# Blinky_board.net
KiCad netlist of a schematic drawn in EAGLE
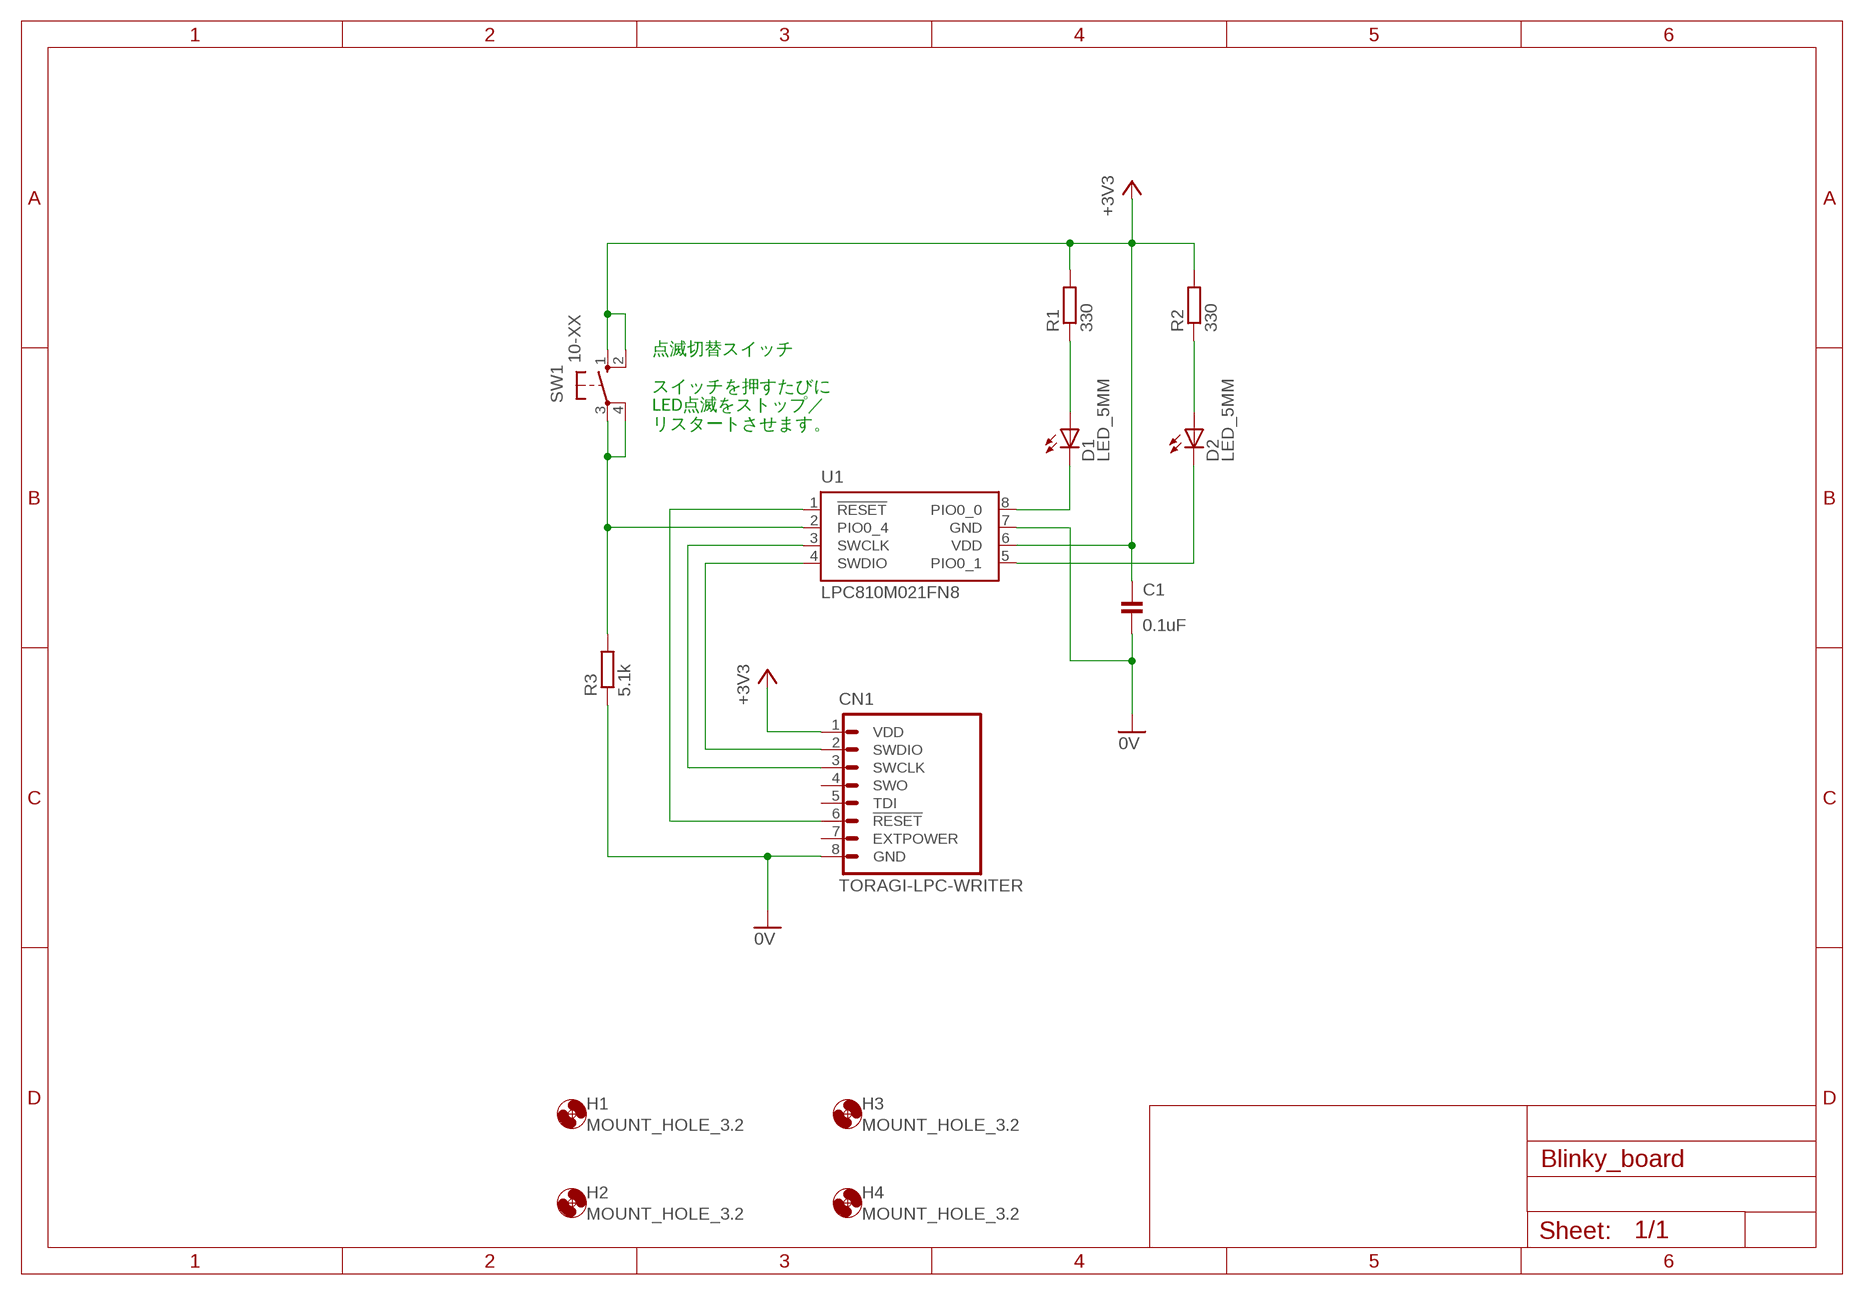
[diagram p0: schematic, sheet 1]

(export (version "E")
  (design (tool "Eeschema 10.0.6"))
  (components
    (comp (ref "C1")
      (value "0.1uF")
      (footprint "eagle-import:CAP_100MIL")
      (libsource (lib "eagle-import") (part "CAP_100MIL"))
    )
    (comp (ref "CN1")
      (value "TORAGI-LPC-WRITER")
      (footprint "eagle-import:TORAGI-LPC-WRITER")
      (libsource (lib "eagle-import") (part "TORAGI-LPC-WRITER"))
    )
    (comp (ref "D1")
      (value "LED_5MM")
      (footprint "eagle-import:LED5MM")
      (libsource (lib "eagle-import") (part "LED_5MM"))
    )
    (comp (ref "D2")
      (value "LED_5MM")
      (footprint "eagle-import:LED5MM")
      (libsource (lib "eagle-import") (part "LED_5MM"))
    )
    (comp (ref "H1")
      (value "MOUNT_HOLE_3.2")
      (footprint "eagle-import:3,2")
      (libsource (lib "eagle-import") (part "MOUNT_HOLE_3.2"))
    )
    (comp (ref "H2")
      (value "MOUNT_HOLE_3.2")
      (footprint "eagle-import:3,2")
      (libsource (lib "eagle-import") (part "MOUNT_HOLE_3.2"))
    )
    (comp (ref "H3")
      (value "MOUNT_HOLE_3.2")
      (footprint "eagle-import:3,2")
      (libsource (lib "eagle-import") (part "MOUNT_HOLE_3.2"))
    )
    (comp (ref "H4")
      (value "MOUNT_HOLE_3.2")
      (footprint "eagle-import:3,2")
      (libsource (lib "eagle-import") (part "MOUNT_HOLE_3.2"))
    )
    (comp (ref "R1")
      (value "330")
      (footprint "eagle-import:RESISTOR_0204_200MIL")
      (libsource (lib "eagle-import") (part "RESISTOR_200MIL"))
    )
    (comp (ref "R2")
      (value "330")
      (footprint "eagle-import:RESISTOR_0204_200MIL")
      (libsource (lib "eagle-import") (part "RESISTOR_200MIL"))
    )
    (comp (ref "R3")
      (value "5.1k")
      (footprint "eagle-import:RESISTOR_0204_200MIL")
      (libsource (lib "eagle-import") (part "RESISTOR_200MIL"))
    )
    (comp (ref "SW1")
      (value "10-XX")
      (footprint "eagle-import:B3F-10XX")
      (libsource (lib "eagle-import") (part "10-XX"))
    )
    (comp (ref "U1")
      (value "LPC810M021FN8")
      (footprint "eagle-import:DIL08")
      (libsource (lib "eagle-import") (part "LPC810M021FN8"))
    )
  )
  (nets
    (net (code "1") (name "+3V3") (class "Default")
      (node (ref "C1") (pin "1") (pinfunction "1_1") (pintype "passive"))
      (node (ref "CN1") (pin "1") (pinfunction "VDD_1") (pintype "passive"))
      (node (ref "R1") (pin "2") (pinfunction "2_2") (pintype "passive"))
      (node (ref "R2") (pin "2") (pinfunction "2_2") (pintype "passive"))
      (node (ref "SW1") (pin "1") (pinfunction "S_1") (pintype "passive"))
      (node (ref "SW1") (pin "2") (pinfunction "S1_2") (pintype "passive"))
      (node (ref "U1") (pin "6") (pinfunction "VDD_6") (pintype "passive"))
    )
    (net (code "2") (name "0V") (class "Default")
      (node (ref "C1") (pin "2") (pinfunction "2_2") (pintype "passive"))
      (node (ref "CN1") (pin "8") (pinfunction "GND_8") (pintype "passive"))
      (node (ref "R3") (pin "1") (pinfunction "1_1") (pintype "passive"))
      (node (ref "U1") (pin "7") (pinfunction "GND_7") (pintype "passive"))
    )
    (net (code "3") (name "Net-(CN1-SWCLK)") (class "Default")
      (node (ref "CN1") (pin "3") (pinfunction "SWCLK_3") (pintype "bidirectional"))
      (node (ref "U1") (pin "3") (pinfunction "SWCLK_3") (pintype "bidirectional"))
    )
    (net (code "4") (name "Net-(CN1-SWDIO)") (class "Default")
      (node (ref "CN1") (pin "2") (pinfunction "SWDIO_2") (pintype "bidirectional"))
      (node (ref "U1") (pin "4") (pinfunction "SWDIO_4") (pintype "bidirectional"))
    )
    (net (code "5") (name "Net-(CN1-~{RESET})") (class "Default")
      (node (ref "CN1") (pin "6") (pinfunction "~{RESET}_6") (pintype "bidirectional"))
      (node (ref "U1") (pin "1") (pinfunction "~{RESET}_1") (pintype "bidirectional"))
    )
    (net (code "6") (name "Net-(D1-C)") (class "Default")
      (node (ref "D1") (pin "K") (pinfunction "C_K") (pintype "passive"))
      (node (ref "U1") (pin "8") (pinfunction "PIO0_0_8") (pintype "bidirectional"))
    )
    (net (code "7") (name "Net-(D1-PadA)") (class "Default")
      (node (ref "D1") (pin "A") (pinfunction "A_A") (pintype "passive"))
      (node (ref "R1") (pin "1") (pinfunction "1_1") (pintype "passive"))
    )
    (net (code "8") (name "Net-(D2-C)") (class "Default")
      (node (ref "D2") (pin "K") (pinfunction "C_K") (pintype "passive"))
      (node (ref "U1") (pin "5") (pinfunction "PIO0_1_5") (pintype "bidirectional"))
    )
    (net (code "9") (name "Net-(D2-PadA)") (class "Default")
      (node (ref "D2") (pin "A") (pinfunction "A_A") (pintype "passive"))
      (node (ref "R2") (pin "1") (pinfunction "1_1") (pintype "passive"))
    )
    (net (code "10") (name "Net-(SW1-P)") (class "Default")
      (node (ref "R3") (pin "2") (pinfunction "2_2") (pintype "passive"))
      (node (ref "SW1") (pin "3") (pinfunction "P_3") (pintype "passive"))
      (node (ref "SW1") (pin "4") (pinfunction "P1_4") (pintype "passive"))
      (node (ref "U1") (pin "2") (pinfunction "PIO0_4_2") (pintype "bidirectional"))
    )
    (net (code "11") (name "unconnected-(CN1-EXTPOWER-Pad7)") (class "Default")
      (node (ref "CN1") (pin "7") (pinfunction "EXTPOWER_7") (pintype "bidirectional"))
    )
    (net (code "12") (name "unconnected-(CN1-SWO-Pad4)") (class "Default")
      (node (ref "CN1") (pin "4") (pinfunction "SWO_4") (pintype "bidirectional"))
    )
    (net (code "13") (name "unconnected-(CN1-TDI-Pad5)") (class "Default")
      (node (ref "CN1") (pin "5") (pinfunction "TDI_5") (pintype "bidirectional"))
    )
  )
)
